# W706C.net
KiCad netlist of a schematic drawn in EAGLE
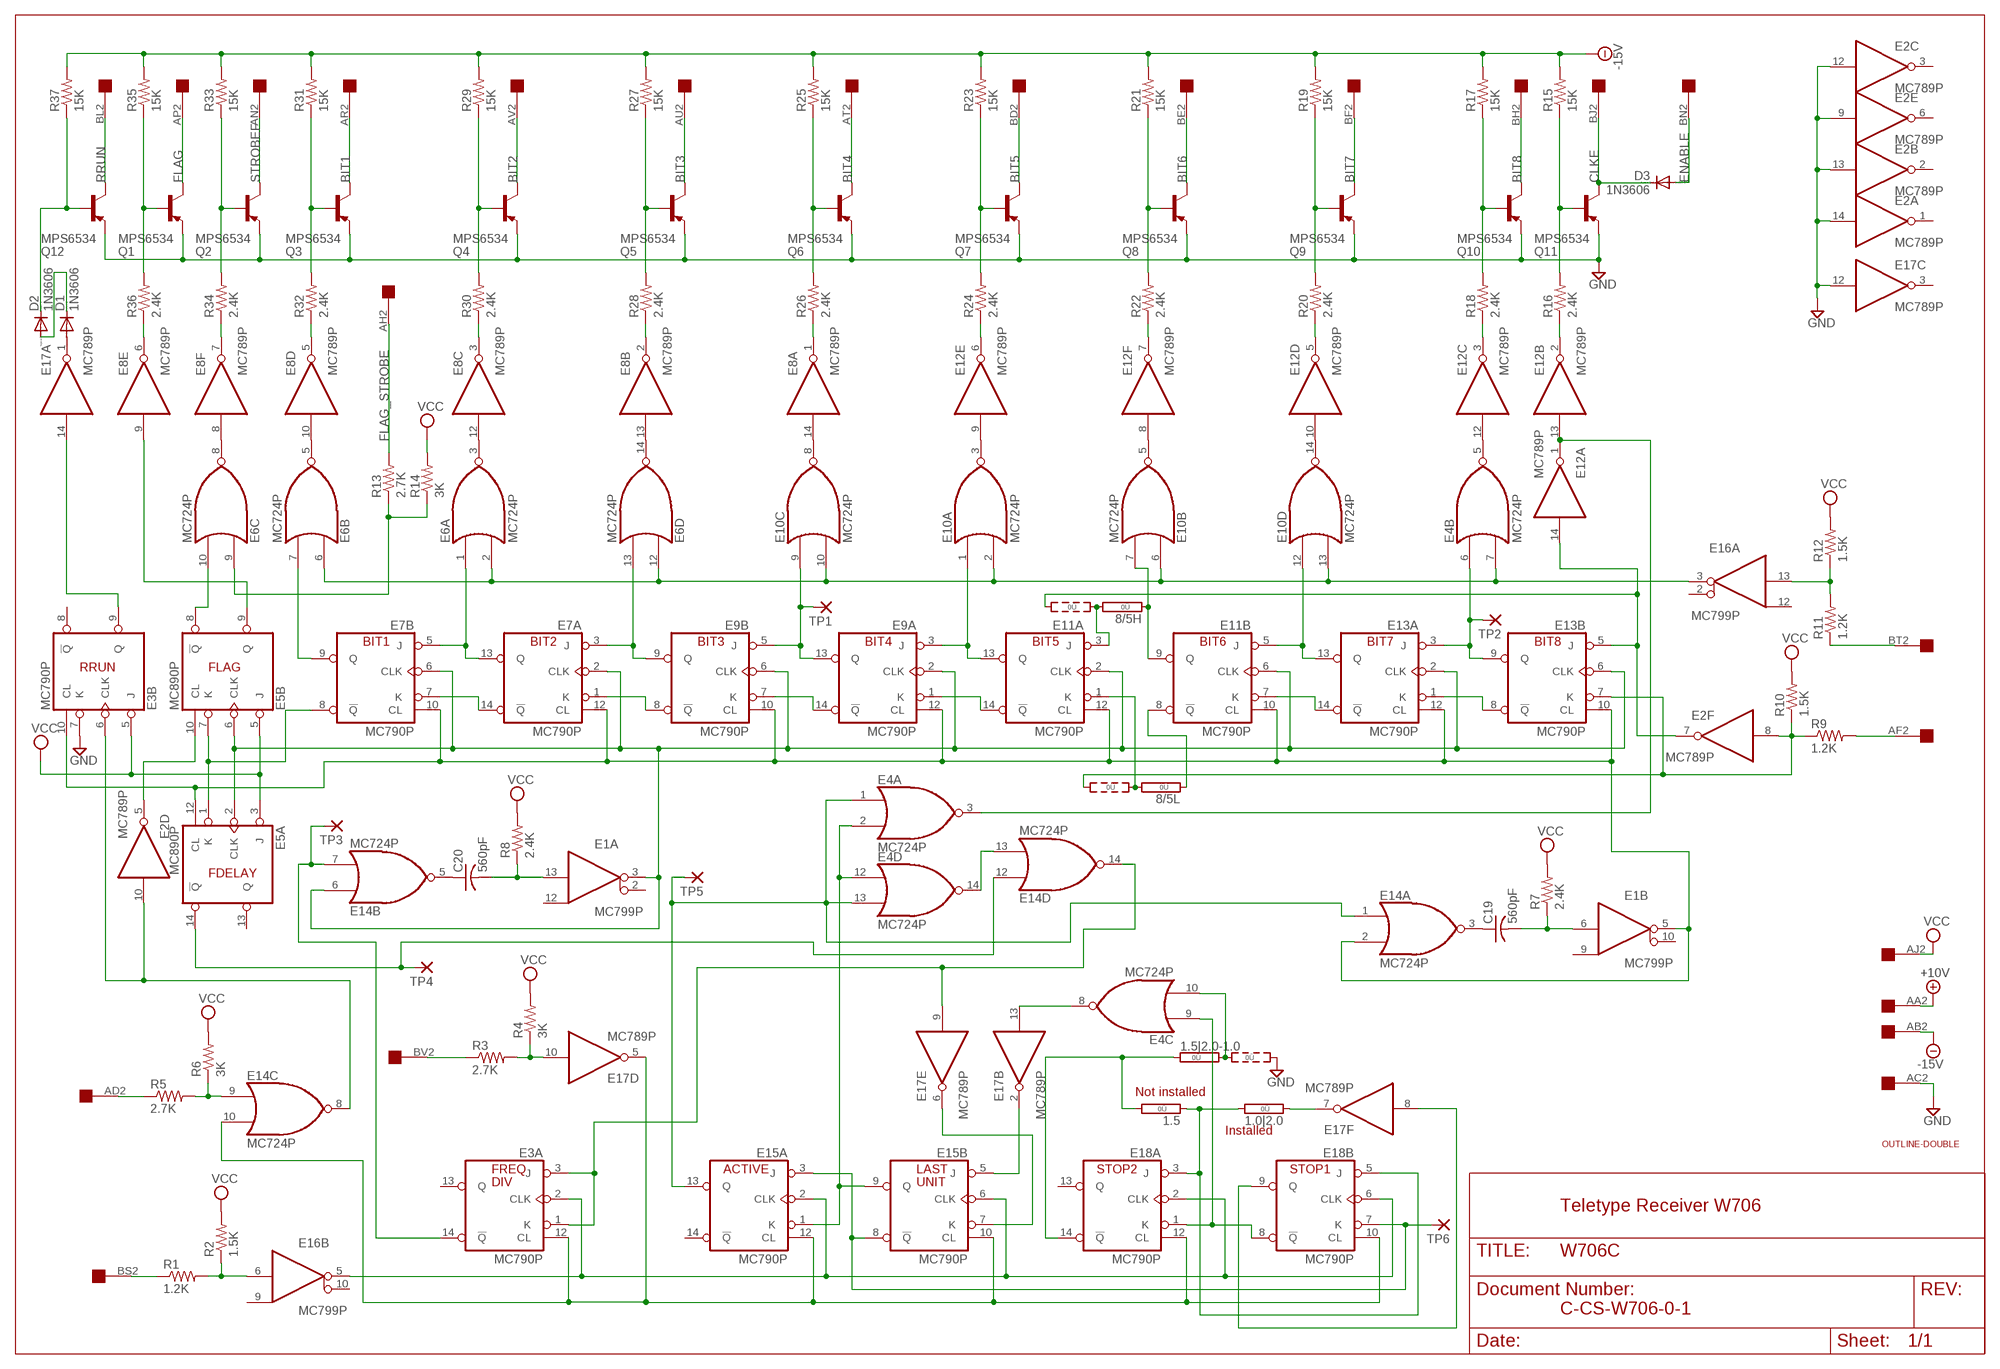
[diagram p0: schematic, sheet 1]

(export (version "E")
  (design (tool "Eeschema 10.0.6"))
  (components
    (comp (ref "1.0|2.0")
      (value "0R")
      (footprint "eagle-import:0R_10")
      (libsource (lib "eagle-import") (part "0R"))
    )
    (comp (ref "1.5")
      (value "0R")
      (footprint "eagle-import:0R_10")
      (libsource (lib "eagle-import") (part "0R"))
    )
    (comp (ref "1.5|2.0-1.0")
      (value "0R2")
      (footprint "eagle-import:0R2_10")
      (libsource (lib "eagle-import") (part "0R2"))
    )
    (comp (ref "8/5H")
      (value "0R2")
      (footprint "eagle-import:0R2_10")
      (libsource (lib "eagle-import") (part "0R2"))
    )
    (comp (ref "8/5L")
      (value "0R2")
      (footprint "eagle-import:0R2_10")
      (libsource (lib "eagle-import") (part "0R2"))
    )
    (comp (ref "C19")
      (value "560pF")
      (footprint "eagle-import:C050-025X075")
      (libsource (lib "eagle-import") (part "C-US050-025X075"))
    )
    (comp (ref "C20")
      (value "560pF")
      (footprint "eagle-import:C050-025X075")
      (libsource (lib "eagle-import") (part "C-US050-025X075"))
    )
    (comp (ref "D1")
      (value "1N3606")
      (footprint "eagle-import:DO35-10")
      (libsource (lib "eagle-import") (part "1N4148DO35-10"))
    )
    (comp (ref "D2")
      (value "1N3606")
      (footprint "eagle-import:DO35-10")
      (libsource (lib "eagle-import") (part "1N4148DO35-10"))
    )
    (comp (ref "D3")
      (value "1N3606")
      (footprint "eagle-import:DO35-10")
      (libsource (lib "eagle-import") (part "1N4148DO35-10"))
    )
    (comp (ref "E1")
      (value "MC799P")
      (footprint "eagle-import:DIL14")
      (libsource (lib "eagle-import") (part "MC899P"))
    )
    (comp (ref "E2")
      (value "MC789P")
      (footprint "eagle-import:DIL14")
      (libsource (lib "eagle-import") (part "MC889P"))
    )
    (comp (ref "E3")
      (value "MC790P")
      (footprint "eagle-import:DIL14")
      (libsource (lib "eagle-import") (part "MC890P"))
    )
    (comp (ref "E4")
      (value "MC724P")
      (footprint "eagle-import:DIL14")
      (libsource (lib "eagle-import") (part "MC824P"))
    )
    (comp (ref "E5")
      (value "MC890P")
      (footprint "eagle-import:DIL14")
      (libsource (lib "eagle-import") (part "MC890P"))
    )
    (comp (ref "E6")
      (value "MC724P")
      (footprint "eagle-import:DIL14")
      (libsource (lib "eagle-import") (part "MC824P"))
    )
    (comp (ref "E7")
      (value "MC790P")
      (footprint "eagle-import:DIL14")
      (libsource (lib "eagle-import") (part "MC890P"))
    )
    (comp (ref "E8")
      (value "MC789P")
      (footprint "eagle-import:DIL14")
      (libsource (lib "eagle-import") (part "MC889P"))
    )
    (comp (ref "E9")
      (value "MC790P")
      (footprint "eagle-import:DIL14")
      (libsource (lib "eagle-import") (part "MC890P"))
    )
    (comp (ref "E10")
      (value "MC724P")
      (footprint "eagle-import:DIL14")
      (libsource (lib "eagle-import") (part "MC824P"))
    )
    (comp (ref "E11")
      (value "MC790P")
      (footprint "eagle-import:DIL14")
      (libsource (lib "eagle-import") (part "MC890P"))
    )
    (comp (ref "E12")
      (value "MC789P")
      (footprint "eagle-import:DIL14")
      (libsource (lib "eagle-import") (part "MC889P"))
    )
    (comp (ref "E13")
      (value "MC790P")
      (footprint "eagle-import:DIL14")
      (libsource (lib "eagle-import") (part "MC890P"))
    )
    (comp (ref "E14")
      (value "MC724P")
      (footprint "eagle-import:DIL14")
      (libsource (lib "eagle-import") (part "MC824P"))
    )
    (comp (ref "E15")
      (value "MC790P")
      (footprint "eagle-import:DIL14")
      (libsource (lib "eagle-import") (part "MC890P"))
    )
    (comp (ref "E16")
      (value "MC799P")
      (footprint "eagle-import:DIL14")
      (libsource (lib "eagle-import") (part "MC899P"))
    )
    (comp (ref "E17")
      (value "MC789P")
      (footprint "eagle-import:DIL14")
      (libsource (lib "eagle-import") (part "MC889P"))
    )
    (comp (ref "E18")
      (value "MC790P")
      (footprint "eagle-import:DIL14")
      (libsource (lib "eagle-import") (part "MC890P"))
    )
    (comp (ref "Q1")
      (value "MPS6534")
      (footprint "eagle-import:TO39")
      (libsource (lib "eagle-import") (part "2N2904"))
    )
    (comp (ref "Q2")
      (value "MPS6534")
      (footprint "eagle-import:TO39")
      (libsource (lib "eagle-import") (part "2N2904"))
    )
    (comp (ref "Q3")
      (value "MPS6534")
      (footprint "eagle-import:TO39")
      (libsource (lib "eagle-import") (part "2N2904"))
    )
    (comp (ref "Q4")
      (value "MPS6534")
      (footprint "eagle-import:TO39")
      (libsource (lib "eagle-import") (part "2N2904"))
    )
    (comp (ref "Q5")
      (value "MPS6534")
      (footprint "eagle-import:TO39")
      (libsource (lib "eagle-import") (part "2N2904"))
    )
    (comp (ref "Q6")
      (value "MPS6534")
      (footprint "eagle-import:TO39")
      (libsource (lib "eagle-import") (part "2N2904"))
    )
    (comp (ref "Q7")
      (value "MPS6534")
      (footprint "eagle-import:TO39")
      (libsource (lib "eagle-import") (part "2N2904"))
    )
    (comp (ref "Q8")
      (value "MPS6534")
      (footprint "eagle-import:TO39")
      (libsource (lib "eagle-import") (part "2N2904"))
    )
    (comp (ref "Q9")
      (value "MPS6534")
      (footprint "eagle-import:TO39")
      (libsource (lib "eagle-import") (part "2N2904"))
    )
    (comp (ref "Q10")
      (value "MPS6534")
      (footprint "eagle-import:TO39")
      (libsource (lib "eagle-import") (part "2N2904"))
    )
    (comp (ref "Q11")
      (value "MPS6534")
      (footprint "eagle-import:TO39")
      (libsource (lib "eagle-import") (part "2N2904"))
    )
    (comp (ref "Q12")
      (value "MPS6534")
      (footprint "eagle-import:TO39")
      (libsource (lib "eagle-import") (part "2N2904"))
    )
    (comp (ref "R1")
      (value "1.2K")
      (footprint "eagle-import:0207_10")
      (libsource (lib "eagle-import") (part "R-US_0207/10"))
    )
    (comp (ref "R2")
      (value "1.5K")
      (footprint "eagle-import:0207_10")
      (libsource (lib "eagle-import") (part "R-US_0207/10"))
    )
    (comp (ref "R3")
      (value "2.7K")
      (footprint "eagle-import:0207_10")
      (libsource (lib "eagle-import") (part "R-US_0207/10"))
    )
    (comp (ref "R4")
      (value "3K")
      (footprint "eagle-import:0207_10")
      (libsource (lib "eagle-import") (part "R-US_0207/10"))
    )
    (comp (ref "R5")
      (value "2.7K")
      (footprint "eagle-import:0207_10")
      (libsource (lib "eagle-import") (part "R-US_0207/10"))
    )
    (comp (ref "R6")
      (value "3K")
      (footprint "eagle-import:0207_10")
      (libsource (lib "eagle-import") (part "R-US_0207/10"))
    )
    (comp (ref "R7")
      (value "2.4K")
      (footprint "eagle-import:0207_10")
      (libsource (lib "eagle-import") (part "R-US_0207/10"))
    )
    (comp (ref "R8")
      (value "2.4K")
      (footprint "eagle-import:0207_10")
      (libsource (lib "eagle-import") (part "R-US_0207/10"))
    )
    (comp (ref "R9")
      (value "1.2K")
      (footprint "eagle-import:0207_10")
      (libsource (lib "eagle-import") (part "R-US_0207/10"))
    )
    (comp (ref "R10")
      (value "1.5K")
      (footprint "eagle-import:0207_10")
      (libsource (lib "eagle-import") (part "R-US_0207/10"))
    )
    (comp (ref "R11")
      (value "1.2K")
      (footprint "eagle-import:0207_10")
      (libsource (lib "eagle-import") (part "R-US_0207/10"))
    )
    (comp (ref "R12")
      (value "1.5K")
      (footprint "eagle-import:0207_10")
      (libsource (lib "eagle-import") (part "R-US_0207/10"))
    )
    (comp (ref "R13")
      (value "2.7K")
      (footprint "eagle-import:0207_10")
      (libsource (lib "eagle-import") (part "R-US_0207/10"))
    )
    (comp (ref "R14")
      (value "3K")
      (footprint "eagle-import:0207_10")
      (libsource (lib "eagle-import") (part "R-US_0207/10"))
    )
    (comp (ref "R15")
      (value "15K")
      (footprint "eagle-import:0207_10")
      (libsource (lib "eagle-import") (part "R-US_0207/10"))
    )
    (comp (ref "R16")
      (value "2.4K")
      (footprint "eagle-import:0207_10")
      (libsource (lib "eagle-import") (part "R-US_0207/10"))
    )
    (comp (ref "R17")
      (value "15K")
      (footprint "eagle-import:0207_10")
      (libsource (lib "eagle-import") (part "R-US_0207/10"))
    )
    (comp (ref "R18")
      (value "2.4K")
      (footprint "eagle-import:0207_10")
      (libsource (lib "eagle-import") (part "R-US_0207/10"))
    )
    (comp (ref "R19")
      (value "15K")
      (footprint "eagle-import:0207_10")
      (libsource (lib "eagle-import") (part "R-US_0207/10"))
    )
    (comp (ref "R20")
      (value "2.4K")
      (footprint "eagle-import:0207_10")
      (libsource (lib "eagle-import") (part "R-US_0207/10"))
    )
    (comp (ref "R21")
      (value "15K")
      (footprint "eagle-import:0207_10")
      (libsource (lib "eagle-import") (part "R-US_0207/10"))
    )
    (comp (ref "R22")
      (value "2.4K")
      (footprint "eagle-import:0207_10")
      (libsource (lib "eagle-import") (part "R-US_0207/10"))
    )
    (comp (ref "R23")
      (value "15K")
      (footprint "eagle-import:0207_10")
      (libsource (lib "eagle-import") (part "R-US_0207/10"))
    )
    (comp (ref "R24")
      (value "2.4K")
      (footprint "eagle-import:0207_10")
      (libsource (lib "eagle-import") (part "R-US_0207/10"))
    )
    (comp (ref "R25")
      (value "15K")
      (footprint "eagle-import:0207_10")
      (libsource (lib "eagle-import") (part "R-US_0207/10"))
    )
    (comp (ref "R26")
      (value "2.4K")
      (footprint "eagle-import:0207_10")
      (libsource (lib "eagle-import") (part "R-US_0207/10"))
    )
    (comp (ref "R27")
      (value "15K")
      (footprint "eagle-import:0207_10")
      (libsource (lib "eagle-import") (part "R-US_0207/10"))
    )
    (comp (ref "R28")
      (value "2.4K")
      (footprint "eagle-import:0207_10")
      (libsource (lib "eagle-import") (part "R-US_0207/10"))
    )
    (comp (ref "R29")
      (value "15K")
      (footprint "eagle-import:0207_10")
      (libsource (lib "eagle-import") (part "R-US_0207/10"))
    )
    (comp (ref "R30")
      (value "2.4K")
      (footprint "eagle-import:0207_10")
      (libsource (lib "eagle-import") (part "R-US_0207/10"))
    )
    (comp (ref "R31")
      (value "15K")
      (footprint "eagle-import:0207_10")
      (libsource (lib "eagle-import") (part "R-US_0207/10"))
    )
    (comp (ref "R32")
      (value "2.4K")
      (footprint "eagle-import:0207_10")
      (libsource (lib "eagle-import") (part "R-US_0207/10"))
    )
    (comp (ref "R33")
      (value "15K")
      (footprint "eagle-import:0207_10")
      (libsource (lib "eagle-import") (part "R-US_0207/10"))
    )
    (comp (ref "R34")
      (value "2.4K")
      (footprint "eagle-import:0207_10")
      (libsource (lib "eagle-import") (part "R-US_0207/10"))
    )
    (comp (ref "R35")
      (value "15K")
      (footprint "eagle-import:0207_10")
      (libsource (lib "eagle-import") (part "R-US_0207/10"))
    )
    (comp (ref "R36")
      (value "2.4K")
      (footprint "eagle-import:0207_10")
      (libsource (lib "eagle-import") (part "R-US_0207/10"))
    )
    (comp (ref "R37")
      (value "15K")
      (footprint "eagle-import:0207_10")
      (libsource (lib "eagle-import") (part "R-US_0207/10"))
    )
    (comp (ref "TP1")
      (value "3,17/1,3")
      (footprint "eagle-import:3,17_1,3")
      (libsource (lib "eagle-import") (part "3,17/1,3"))
    )
    (comp (ref "TP2")
      (value "3,17/1,3")
      (footprint "eagle-import:3,17_1,3")
      (libsource (lib "eagle-import") (part "3,17/1,3"))
    )
    (comp (ref "TP3")
      (value "3,17/1,3")
      (footprint "eagle-import:3,17_1,3")
      (libsource (lib "eagle-import") (part "3,17/1,3"))
    )
    (comp (ref "TP4")
      (value "3,17/1,3")
      (footprint "eagle-import:3,17_1,3")
      (libsource (lib "eagle-import") (part "3,17/1,3"))
    )
    (comp (ref "TP5")
      (value "3,17/1,3")
      (footprint "eagle-import:3,17_1,3")
      (libsource (lib "eagle-import") (part "3,17/1,3"))
    )
    (comp (ref "TP6")
      (value "3,17/1,3")
      (footprint "eagle-import:3,17_1,3")
      (libsource (lib "eagle-import") (part "3,17/1,3"))
    )
    (comp (ref "U$1")
      (value "OUTLINE-DOUBLE")
      (footprint "eagle-import:DOUBLE")
      (libsource (lib "eagle-import") (part "OUTLINE-DOUBLE"))
    )
    (comp (ref "U$2")
      (value "DOUBLE")
      (footprint "eagle-import:EDGE-CON4")
      (libsource (lib "eagle-import") (part "DOUBLE"))
    )
  )
  (nets
    (net (code "1") (name "+10V") (class "Default")
      (node (ref "U$2") (pin "AA2") (pinfunction "1_AA2") (pintype "bidirectional"))
    )
    (net (code "2") (name "-15V") (class "Default")
      (node (ref "R15") (pin "2") (pinfunction "2_2") (pintype "passive"))
      (node (ref "R17") (pin "2") (pinfunction "2_2") (pintype "passive"))
      (node (ref "R19") (pin "2") (pinfunction "2_2") (pintype "passive"))
      (node (ref "R21") (pin "2") (pinfunction "2_2") (pintype "passive"))
      (node (ref "R23") (pin "2") (pinfunction "2_2") (pintype "passive"))
      (node (ref "R25") (pin "2") (pinfunction "2_2") (pintype "passive"))
      (node (ref "R27") (pin "2") (pinfunction "2_2") (pintype "passive"))
      (node (ref "R29") (pin "2") (pinfunction "2_2") (pintype "passive"))
      (node (ref "R31") (pin "2") (pinfunction "2_2") (pintype "passive"))
      (node (ref "R33") (pin "2") (pinfunction "2_2") (pintype "passive"))
      (node (ref "R35") (pin "2") (pinfunction "2_2") (pintype "passive"))
      (node (ref "R37") (pin "2") (pinfunction "2_2") (pintype "passive"))
      (node (ref "U$2") (pin "AB2") (pinfunction "1_AB2") (pintype "bidirectional"))
    )
    (net (code "3") (name "/BIT1") (class "Default")
      (node (ref "Q3") (pin "3") (pinfunction "C_3") (pintype "passive"))
      (node (ref "U$2") (pin "AR2") (pinfunction "1_AR2") (pintype "bidirectional"))
    )
    (net (code "4") (name "/BIT2") (class "Default")
      (node (ref "Q4") (pin "3") (pinfunction "C_3") (pintype "passive"))
      (node (ref "U$2") (pin "AV2") (pinfunction "1_AV2") (pintype "bidirectional"))
    )
    (net (code "5") (name "/BIT3") (class "Default")
      (node (ref "Q5") (pin "3") (pinfunction "C_3") (pintype "passive"))
      (node (ref "U$2") (pin "AU2") (pinfunction "1_AU2") (pintype "bidirectional"))
    )
    (net (code "6") (name "/BIT4") (class "Default")
      (node (ref "Q6") (pin "3") (pinfunction "C_3") (pintype "passive"))
      (node (ref "U$2") (pin "AT2") (pinfunction "1_AT2") (pintype "bidirectional"))
    )
    (net (code "7") (name "/BIT5") (class "Default")
      (node (ref "Q7") (pin "3") (pinfunction "C_3") (pintype "passive"))
      (node (ref "U$2") (pin "BD2") (pinfunction "1_BD2") (pintype "bidirectional"))
    )
    (net (code "8") (name "/BIT6") (class "Default")
      (node (ref "Q8") (pin "3") (pinfunction "C_3") (pintype "passive"))
      (node (ref "U$2") (pin "BE2") (pinfunction "1_BE2") (pintype "bidirectional"))
    )
    (net (code "9") (name "/BIT7") (class "Default")
      (node (ref "Q9") (pin "3") (pinfunction "C_3") (pintype "passive"))
      (node (ref "U$2") (pin "BF2") (pinfunction "1_BF2") (pintype "bidirectional"))
    )
    (net (code "10") (name "/BIT8") (class "Default")
      (node (ref "Q10") (pin "3") (pinfunction "C_3") (pintype "passive"))
      (node (ref "U$2") (pin "BH2") (pinfunction "1_BH2") (pintype "bidirectional"))
    )
    (net (code "11") (name "/CLKE") (class "Default")
      (node (ref "D3") (pin "C") (pinfunction "C_C") (pintype "passive"))
      (node (ref "Q11") (pin "3") (pinfunction "C_3") (pintype "passive"))
      (node (ref "U$2") (pin "BJ2") (pinfunction "1_BJ2") (pintype "bidirectional"))
    )
    (net (code "12") (name "/ENABLE") (class "Default")
      (node (ref "D3") (pin "A") (pinfunction "A_A") (pintype "passive"))
      (node (ref "U$2") (pin "BN2") (pinfunction "1_BN2") (pintype "bidirectional"))
    )
    (net (code "13") (name "/FLAG") (class "Default")
      (node (ref "Q1") (pin "3") (pinfunction "C_3") (pintype "passive"))
      (node (ref "U$2") (pin "AP2") (pinfunction "1_AP2") (pintype "bidirectional"))
    )
    (net (code "14") (name "/FLAG_STROBE") (class "Default")
      (node (ref "R13") (pin "2") (pinfunction "2_2") (pintype "passive"))
      (node (ref "U$2") (pin "AH2") (pinfunction "1_AH2") (pintype "bidirectional"))
    )
    (net (code "15") (name "/RRUN") (class "Default")
      (node (ref "Q12") (pin "3") (pinfunction "C_3") (pintype "passive"))
      (node (ref "U$2") (pin "BL2") (pinfunction "1_BL2") (pintype "bidirectional"))
    )
    (net (code "16") (name "/STROBEF") (class "Default")
      (node (ref "Q2") (pin "3") (pinfunction "C_3") (pintype "passive"))
      (node (ref "U$2") (pin "AN2") (pinfunction "1_AN2") (pintype "bidirectional"))
    )
    (net (code "17") (name "GND") (class "Default")
      (node (ref "1.5|2.0-1.0") (pin "3") (pinfunction "3_3") (pintype "passive"))
      (node (ref "E17") (pin "12") (pinfunction "I_12") (pintype "input"))
      (node (ref "E2") (pin "12") (pinfunction "I_12") (pintype "input"))
      (node (ref "E2") (pin "13") (pinfunction "I_13") (pintype "input"))
      (node (ref "E2") (pin "14") (pinfunction "I_14") (pintype "input"))
      (node (ref "E2") (pin "9") (pinfunction "I_9") (pintype "input"))
      (node (ref "E3") (pin "7") (pinfunction "K_7") (pintype "input"))
      (node (ref "Q1") (pin "1") (pinfunction "E_1") (pintype "passive"))
      (node (ref "Q10") (pin "1") (pinfunction "E_1") (pintype "passive"))
      (node (ref "Q11") (pin "1") (pinfunction "E_1") (pintype "passive"))
      (node (ref "Q12") (pin "1") (pinfunction "E_1") (pintype "passive"))
      (node (ref "Q2") (pin "1") (pinfunction "E_1") (pintype "passive"))
      (node (ref "Q3") (pin "1") (pinfunction "E_1") (pintype "passive"))
      (node (ref "Q4") (pin "1") (pinfunction "E_1") (pintype "passive"))
      (node (ref "Q5") (pin "1") (pinfunction "E_1") (pintype "passive"))
      (node (ref "Q6") (pin "1") (pinfunction "E_1") (pintype "passive"))
      (node (ref "Q7") (pin "1") (pinfunction "E_1") (pintype "passive"))
      (node (ref "Q8") (pin "1") (pinfunction "E_1") (pintype "passive"))
      (node (ref "Q9") (pin "1") (pinfunction "E_1") (pintype "passive"))
      (node (ref "U$2") (pin "AC2") (pinfunction "1_AC2") (pintype "bidirectional"))
    )
    (net (code "18") (name "Net-(D1-PadC)") (class "Default")
      (node (ref "D1") (pin "C") (pinfunction "C_C") (pintype "passive"))
      (node (ref "D2") (pin "A") (pinfunction "A_A") (pintype "passive"))
    )
    (net (code "19") (name "Net-(E1A-I)") (class "Default")
      (node (ref "C20") (pin "2") (pinfunction "2_2") (pintype "passive"))
      (node (ref "E1") (pin "13") (pinfunction "I_13") (pintype "input"))
      (node (ref "R8") (pin "1") (pinfunction "1_1") (pintype "passive"))
    )
    (net (code "20") (name "Net-(E1B-I)") (class "Default")
      (node (ref "C19") (pin "2") (pinfunction "2_2") (pintype "passive"))
      (node (ref "E1") (pin "6") (pinfunction "I_6") (pintype "input"))
      (node (ref "R7") (pin "1") (pinfunction "1_1") (pintype "passive"))
    )
    (net (code "21") (name "Net-(E2D-O)") (class "Default")
      (node (ref "E2") (pin "5") (pinfunction "O_5") (pintype "output"))
      (node (ref "E5") (pin "10") (pinfunction "CL_10") (pintype "input"))
    )
    (net (code "22") (name "Net-(E4C-I1)") (class "Default")
      (node (ref "1.5|2.0-1.0") (pin "2") (pinfunction "2_2") (pintype "passive"))
      (node (ref "E4") (pin "10") (pinfunction "I1_10") (pintype "input"))
    )
    (net (code "23") (name "Net-(E5A-K)") (class "Default")
      (node (ref "E5") (pin "1") (pinfunction "K_1") (pintype "input"))
      (node (ref "E5") (pin "7") (pinfunction "K_7") (pintype "input"))
      (node (ref "E7") (pin "8") (pinfunction "~{Q}_8") (pintype "output"))
    )
    (net (code "24") (name "Net-(E5B-Q)") (class "Default")
      (node (ref "E5") (pin "9") (pinfunction "Q_9") (pintype "output"))
      (node (ref "E8") (pin "9") (pinfunction "I_9") (pintype "input"))
    )
    (net (code "25") (name "Net-(E5B-~{Q})") (class "Default")
      (node (ref "E5") (pin "8") (pinfunction "~{Q}_8") (pintype "output"))
      (node (ref "E6") (pin "10") (pinfunction "I1_10") (pintype "input"))
    )
    (net (code "26") (name "Net-(E6A-I0)") (class "Default")
      (node (ref "E6") (pin "1") (pinfunction "I0_1") (pintype "input"))
      (node (ref "E7") (pin "13") (pinfunction "Q_13") (pintype "output"))
      (node (ref "E7") (pin "5") (pinfunction "J_5") (pintype "input"))
    )
    (net (code "27") (name "Net-(E6A-O)") (class "Default")
      (node (ref "E6") (pin "3") (pinfunction "O_3") (pintype "output"))
      (node (ref "E8") (pin "12") (pinfunction "I_12") (pintype "input"))
    )
    (net (code "28") (name "Net-(E6B-I1)") (class "Default")
      (node (ref "E6") (pin "7") (pinfunction "I1_7") (pintype "input"))
      (node (ref "E7") (pin "9") (pinfunction "Q_9") (pintype "output"))
    )
    (net (code "29") (name "Net-(E6B-O)") (class "Default")
      (node (ref "E6") (pin "5") (pinfunction "O_5") (pintype "output"))
      (node (ref "E8") (pin "10") (pinfunction "I_10") (pintype "input"))
    )
    (net (code "30") (name "Net-(E6C-I0)") (class "Default")
      (node (ref "E6") (pin "9") (pinfunction "I0_9") (pintype "input"))
      (node (ref "R13") (pin "1") (pinfunction "1_1") (pintype "passive"))
      (node (ref "R14") (pin "1") (pinfunction "1_1") (pintype "passive"))
    )
    (net (code "31") (name "Net-(E6C-O)") (class "Default")
      (node (ref "E6") (pin "8") (pinfunction "O_8") (pintype "output"))
      (node (ref "E8") (pin "8") (pinfunction "I_8") (pintype "input"))
    )
    (net (code "32") (name "Net-(E6D-I1)") (class "Default")
      (node (ref "E6") (pin "13") (pinfunction "I1_13") (pintype "input"))
      (node (ref "E7") (pin "3") (pinfunction "J_3") (pintype "input"))
      (node (ref "E9") (pin "9") (pinfunction "Q_9") (pintype "output"))
    )
    (net (code "33") (name "Net-(E6D-O)") (class "Default")
      (node (ref "E6") (pin "14") (pinfunction "O_14") (pintype "output"))
      (node (ref "E8") (pin "13") (pinfunction "I_13") (pintype "input"))
    )
    (net (code "34") (name "Net-(E7A-K)") (class "Default")
      (node (ref "E7") (pin "1") (pinfunction "K_1") (pintype "input"))
      (node (ref "E9") (pin "8") (pinfunction "~{Q}_8") (pintype "output"))
    )
    (net (code "35") (name "Net-(E7A-~{Q})") (class "Default")
      (node (ref "E7") (pin "14") (pinfunction "~{Q}_14") (pintype "output"))
      (node (ref "E7") (pin "7") (pinfunction "K_7") (pintype "input"))
    )
    (net (code "36") (name "Net-(E8A-O)") (class "Default")
      (node (ref "E8") (pin "1") (pinfunction "O_1") (pintype "output"))
      (node (ref "R26") (pin "1") (pinfunction "1_1") (pintype "passive"))
    )
    (net (code "37") (name "Net-(E8B-O)") (class "Default")
      (node (ref "E8") (pin "2") (pinfunction "O_2") (pintype "output"))
      (node (ref "R28") (pin "1") (pinfunction "1_1") (pintype "passive"))
    )
    (net (code "38") (name "Net-(E8C-O)") (class "Default")
      (node (ref "E8") (pin "3") (pinfunction "O_3") (pintype "output"))
      (node (ref "R30") (pin "1") (pinfunction "1_1") (pintype "passive"))
    )
    (net (code "39") (name "Net-(E8D-O)") (class "Default")
      (node (ref "E8") (pin "5") (pinfunction "O_5") (pintype "output"))
      (node (ref "R32") (pin "1") (pinfunction "1_1") (pintype "passive"))
    )
    (net (code "40") (name "Net-(E8E-O)") (class "Default")
      (node (ref "E8") (pin "6") (pinfunction "O_6") (pintype "output"))
      (node (ref "R36") (pin "1") (pinfunction "1_1") (pintype "passive"))
    )
    (net (code "41") (name "Net-(E8F-O)") (class "Default")
      (node (ref "E8") (pin "7") (pinfunction "O_7") (pintype "output"))
      (node (ref "R34") (pin "1") (pinfunction "1_1") (pintype "passive"))
    )
    (net (code "42") (name "Net-(E9A-~{Q})") (class "Default")
      (node (ref "E9") (pin "14") (pinfunction "~{Q}_14") (pintype "output"))
      (node (ref "E9") (pin "7") (pinfunction "K_7") (pintype "input"))
    )
    (net (code "43") (name "Net-(E10A-I0)") (class "Default")
      (node (ref "E10") (pin "1") (pinfunction "I0_1") (pintype "input"))
      (node (ref "E11") (pin "13") (pinfunction "Q_13") (pintype "output"))
      (node (ref "E9") (pin "3") (pinfunction "J_3") (pintype "input"))
    )
    (net (code "44") (name "Net-(E10A-I1)") (class "Default")
      (node (ref "E10") (pin "10") (pinfunction "I1_10") (pintype "input"))
      (node (ref "E10") (pin "13") (pinfunction "I1_13") (pintype "input"))
      (node (ref "E10") (pin "2") (pinfunction "I1_2") (pintype "input"))
      (node (ref "E10") (pin "6") (pinfunction "I0_6") (pintype "input"))
      (node (ref "E16") (pin "3") (pinfunction "O_3") (pintype "output"))
      (node (ref "E4") (pin "7") (pinfunction "I1_7") (pintype "input"))
      (node (ref "E6") (pin "12") (pinfunction "I0_12") (pintype "input"))
      (node (ref "E6") (pin "2") (pinfunction "I1_2") (pintype "input"))
      (node (ref "E6") (pin "6") (pinfunction "I0_6") (pintype "input"))
    )
    (net (code "45") (name "Net-(E10A-O)") (class "Default")
      (node (ref "E10") (pin "3") (pinfunction "O_3") (pintype "output"))
      (node (ref "E12") (pin "9") (pinfunction "I_9") (pintype "input"))
    )
    (net (code "46") (name "Net-(E10B-I1)") (class "Default")
      (node (ref "8/5H") (pin "1") (pinfunction "1_1") (pintype "passive"))
      (node (ref "E10") (pin "7") (pinfunction "I1_7") (pintype "input"))
      (node (ref "E11") (pin "9") (pinfunction "Q_9") (pintype "output"))
    )
    (net (code "47") (name "Net-(E10B-O)") (class "Default")
      (node (ref "E10") (pin "5") (pinfunction "O_5") (pintype "output"))
      (node (ref "E12") (pin "8") (pinfunction "I_8") (pintype "input"))
    )
    (net (code "48") (name "Net-(E10C-I0)") (class "Default")
      (node (ref "E10") (pin "9") (pinfunction "I0_9") (pintype "input"))
      (node (ref "E9") (pin "13") (pinfunction "Q_13") (pintype "output"))
      (node (ref "E9") (pin "5") (pinfunction "J_5") (pintype "input"))
      (node (ref "TP1") (pin "1") (pinfunction "P_1") (pintype "passive"))
    )
    (net (code "49") (name "Net-(E10C-O)") (class "Default")
      (node (ref "E10") (pin "8") (pinfunction "O_8") (pintype "output"))
      (node (ref "E8") (pin "14") (pinfunction "I_14") (pintype "input"))
    )
    (net (code "50") (name "Net-(E10D-I0)") (class "Default")
      (node (ref "E10") (pin "12") (pinfunction "I0_12") (pintype "input"))
      (node (ref "E11") (pin "5") (pinfunction "J_5") (pintype "input"))
      (node (ref "E13") (pin "13") (pinfunction "Q_13") (pintype "output"))
    )
    (net (code "51") (name "Net-(E10D-O)") (class "Default")
      (node (ref "E10") (pin "14") (pinfunction "O_14") (pintype "output"))
      (node (ref "E12") (pin "10") (pinfunction "I_10") (pintype "input"))
    )
    (net (code "52") (name "Net-(E11A-CL)") (class "Default")
      (node (ref "E1") (pin "5") (pinfunction "O_5") (pintype "output"))
      (node (ref "E11") (pin "10") (pinfunction "CL_10") (pintype "input"))
      (node (ref "E11") (pin "12") (pinfunction "CL_12") (pintype "input"))
      (node (ref "E13") (pin "10") (pinfunction "CL_10") (pintype "input"))
      (node (ref "E13") (pin "12") (pinfunction "CL_12") (pintype "input"))
      (node (ref "E14") (pin "2") (pinfunction "I1_2") (pintype "input"))
      (node (ref "E3") (pin "10") (pinfunction "CL_10") (pintype "input"))
      (node (ref "E5") (pin "12") (pinfunction "CL_12") (pintype "input"))
      (node (ref "E7") (pin "10") (pinfunction "CL_10") (pintype "input"))
      (node (ref "E7") (pin "12") (pinfunction "CL_12") (pintype "input"))
      (node (ref "E9") (pin "10") (pinfunction "CL_10") (pintype "input"))
      (node (ref "E9") (pin "12") (pinfunction "CL_12") (pintype "input"))
    )
    (net (code "53") (name "Net-(E11A-CLK)") (class "Default")
      (node (ref "E1") (pin "3") (pinfunction "O_3") (pintype "output"))
      (node (ref "E11") (pin "2") (pinfunction "CLK_2") (pintype "input"))
      (node (ref "E11") (pin "6") (pinfunction "CLK_6") (pintype "input"))
      (node (ref "E13") (pin "2") (pinfunction "CLK_2") (pintype "input"))
      (node (ref "E13") (pin "6") (pinfunction "CLK_6") (pintype "input"))
      (node (ref "E14") (pin "6") (pinfunction "I0_6") (pintype "input"))
      (node (ref "E5") (pin "2") (pinfunction "CLK_2") (pintype "input"))
      (node (ref "E5") (pin "6") (pinfunction "CLK_6") (pintype "input"))
      (node (ref "E7") (pin "2") (pinfunction "CLK_2") (pintype "input"))
      (node (ref "E7") (pin "6") (pinfunction "CLK_6") (pintype "input"))
      (node (ref "E9") (pin "2") (pinfunction "CLK_2") (pintype "input"))
      (node (ref "E9") (pin "6") (pinfunction "CLK_6") (pintype "input"))
    )
    (net (code "54") (name "Net-(E11A-J)") (class "Default")
      (node (ref "8/5H") (pin "2") (pinfunction "2_2") (pintype "passive"))
      (node (ref "E11") (pin "3") (pinfunction "J_3") (pintype "input"))
    )
    (net (code "55") (name "Net-(E11A-K)") (class "Default")
      (node (ref "8/5L") (pin "2") (pinfunction "2_2") (pintype "passive"))
      (node (ref "E11") (pin "1") (pinfunction "K_1") (pintype "input"))
    )
    (net (code "56") (name "Net-(E11A-~{Q})") (class "Default")
      (node (ref "E11") (pin "14") (pinfunction "~{Q}_14") (pintype "output"))
      (node (ref "E9") (pin "1") (pinfunction "K_1") (pintype "input"))
    )
    (net (code "57") (name "Net-(E11B-K)") (class "Default")
      (node (ref "E11") (pin "7") (pinfunction "K_7") (pintype "input"))
      (node (ref "E13") (pin "14") (pinfunction "~{Q}_14") (pintype "output"))
    )
    (net (code "58") (name "Net-(E11B-~{Q})") (class "Default")
      (node (ref "8/5L") (pin "1") (pinfunction "1_1") (pintype "passive"))
      (node (ref "E11") (pin "8") (pinfunction "~{Q}_8") (pintype "output"))
    )
    (net (code "59") (name "Net-(E12A-I)") (class "Default")
      (node (ref "8/5H") (pin "3") (pinfunction "3_3") (pintype "passive"))
      (node (ref "E12") (pin "14") (pinfunction "I_14") (pintype "input"))
      (node (ref "E13") (pin "5") (pinfunction "J_5") (pintype "input"))
      (node (ref "E2") (pin "7") (pinfunction "O_7") (pintype "output"))
    )
    (net (code "60") (name "Net-(E12A-O)") (class "Default")
      (node (ref "E12") (pin "1") (pinfunction "O_1") (pintype "output"))
      (node (ref "E12") (pin "13") (pinfunction "I_13") (pintype "input"))
      (node (ref "E4") (pin "3") (pinfunction "O_3") (pintype "output"))
    )
    (net (code "61") (name "Net-(E12B-O)") (class "Default")
      (node (ref "E12") (pin "2") (pinfunction "O_2") (pintype "output"))
      (node (ref "R16") (pin "1") (pinfunction "1_1") (pintype "passive"))
    )
    (net (code "62") (name "Net-(E12C-I)") (class "Default")
      (node (ref "E12") (pin "12") (pinfunction "I_12") (pintype "input"))
      (node (ref "E4") (pin "5") (pinfunction "O_5") (pintype "output"))
    )
    (net (code "63") (name "Net-(E12C-O)") (class "Default")
      (node (ref "E12") (pin "3") (pinfunction "O_3") (pintype "output"))
      (node (ref "R18") (pin "1") (pinfunction "1_1") (pintype "passive"))
    )
    (net (code "64") (name "Net-(E12D-O)") (class "Default")
      (node (ref "E12") (pin "5") (pinfunction "O_5") (pintype "output"))
      (node (ref "R20") (pin "1") (pinfunction "1_1") (pintype "passive"))
    )
    (net (code "65") (name "Net-(E12E-O)") (class "Default")
      (node (ref "E12") (pin "6") (pinfunction "O_6") (pintype "output"))
      (node (ref "R24") (pin "1") (pinfunction "1_1") (pintype "passive"))
    )
    (net (code "66") (name "Net-(E12F-O)") (class "Default")
      (node (ref "E12") (pin "7") (pinfunction "O_7") (pintype "output"))
      (node (ref "R22") (pin "1") (pinfunction "1_1") (pintype "passive"))
    )
    (net (code "67") (name "Net-(E13A-J)") (class "Default")
      (node (ref "E13") (pin "3") (pinfunction "J_3") (pintype "input"))
      (node (ref "E13") (pin "9") (pinfunction "Q_9") (pintype "output"))
      (node (ref "E4") (pin "6") (pinfunction "I0_6") (pintype "input"))
      (node (ref "TP2") (pin "1") (pinfunction "P_1") (pintype "passive"))
    )
    (net (code "68") (name "Net-(E13A-K)") (class "Default")
      (node (ref "E13") (pin "1") (pinfunction "K_1") (pintype "input"))
      (node (ref "E13") (pin "8") (pinfunction "~{Q}_8") (pintype "output"))
    )
    (net (code "69") (name "Net-(E13B-K)") (class "Default")
      (node (ref "8/5L") (pin "3") (pinfunction "3_3") (pintype "passive"))
      (node (ref "E13") (pin "7") (pinfunction "K_7") (pintype "input"))
      (node (ref "E2") (pin "8") (pinfunction "I_8") (pintype "input"))
      (node (ref "R10") (pin "1") (pinfunction "1_1") (pintype "passive"))
      (node (ref "R9") (pin "1") (pinfunction "1_1") (pintype "passive"))
    )
    (net (code "70") (name "Net-(E14A-I0)") (class "Default")
      (node (ref "E14") (pin "1") (pinfunction "I0_1") (pintype "input"))
      (node (ref "E15") (pin "13") (pinfunction "Q_13") (pintype "output"))
      (node (ref "E4") (pin "1") (pinfunction "I0_1") (pintype "input"))
      (node (ref "E4") (pin "13") (pinfunction "I1_13") (pintype "input"))
      (node (ref "TP5") (pin "1") (pinfunction "P_1") (pintype "passive"))
    )
    (net (code "71") (name "Net-(E14A-O)") (class "Default")
      (node (ref "C19") (pin "1") (pinfunction "1_1") (pintype "passive"))
      (node (ref "E14") (pin "3") (pinfunction "O_3") (pintype "output"))
    )
    (net (code "72") (name "Net-(E14B-I1)") (class "Default")
      (node (ref "E14") (pin "7") (pinfunction "I1_7") (pintype "input"))
      (node (ref "E3") (pin "14") (pinfunction "~{Q}_14") (pintype "output"))
      (node (ref "TP3") (pin "1") (pinfunction "P_1") (pintype "passive"))
    )
    (net (code "73") (name "Net-(E14B-O)") (class "Default")
      (node (ref "C20") (pin "1") (pinfunction "1_1") (pintype "passive"))
      (node (ref "E14") (pin "5") (pinfunction "O_5") (pintype "output"))
    )
    (net (code "74") (name "Net-(E14C-I0)") (class "Default")
      (node (ref "E14") (pin "9") (pinfunction "I0_9") (pintype "input"))
      (node (ref "R5") (pin "2") (pinfunction "2_2") (pintype "passive"))
      (node (ref "R6") (pin "1") (pinfunction "1_1") (pintype "passive"))
    )
    (net (code "75") (name "Net-(E14C-I1)") (class "Default")
      (node (ref "E14") (pin "10") (pinfunction "I1_10") (pintype "input"))
      (node (ref "E15") (pin "10") (pinfunction "CL_10") (pintype "input"))
      (node (ref "E15") (pin "12") (pinfunction "CL_12") (pintype "input"))
      (node (ref "E17") (pin "5") (pinfunction "O_5") (pintype "output"))
      (node (ref "E18") (pin "10") (pinfunction "CL_10") (pintype "input"))
      (node (ref "E18") (pin "12") (pinfunction "CL_12") (pintype "input"))
      (node (ref "E3") (pin "12") (pinfunction "CL_12") (pintype "input"))
    )
    (net (code "76") (name "Net-(E14C-O)") (class "Default")
      (node (ref "E14") (pin "8") (pinfunction "O_8") (pintype "output"))
      (node (ref "E2") (pin "10") (pinfunction "I_10") (pintype "input"))
      (node (ref "E3") (pin "6") (pinfunction "CLK_6") (pintype "input"))
    )
    (net (code "77") (name "Net-(E14D-I0)") (class "Default")
      (node (ref "E14") (pin "12") (pinfunction "I0_12") (pintype "input"))
      (node (ref "E5") (pin "14") (pinfunction "~{Q}_14") (pintype "output"))
      (node (ref "TP4") (pin "1") (pinfunction "P_1") (pintype "passive"))
    )
    (net (code "78") (name "Net-(E14D-I1)") (class "Default")
      (node (ref "E14") (pin "13") (pinfunction "I1_13") (pintype "input"))
      (node (ref "E4") (pin "14") (pinfunction "O_14") (pintype "output"))
    )
    (net (code "79") (name "Net-(E14D-O)") (class "Default")
      (node (ref "E14") (pin "14") (pinfunction "O_14") (pintype "output"))
      (node (ref "E17") (pin "9") (pinfunction "I_9") (pintype "input"))
      (node (ref "E3") (pin "1") (pinfunction "K_1") (pintype "input"))
      (node (ref "E3") (pin "3") (pinfunction "J_3") (pintype "input"))
    )
    (net (code "80") (name "Net-(E15A-CLK)") (class "Default")
      (node (ref "E15") (pin "2") (pinfunction "CLK_2") (pintype "input"))
      (node (ref "E15") (pin "6") (pinfunction "CLK_6") (pintype "input"))
      (node (ref "E16") (pin "5") (pinfunction "O_5") (pintype "output"))
      (node (ref "E18") (pin "2") (pinfunction "CLK_2") (pintype "input"))
      (node (ref "E18") (pin "6") (pinfunction "CLK_6") (pintype "input"))
      (node (ref "E3") (pin "2") (pinfunction "CLK_2") (pintype "input"))
    )
    (net (code "81") (name "Net-(E15A-J)") (class "Default")
      (node (ref "E15") (pin "3") (pinfunction "J_3") (pintype "input"))
      (node (ref "E15") (pin "8") (pinfunction "~{Q}_8") (pintype "output"))
      (node (ref "E18") (pin "7") (pinfunction "K_7") (pintype "input"))
      (node (ref "TP6") (pin "1") (pinfunction "P_1") (pintype "passive"))
    )
    (net (code "82") (name "Net-(E15A-K)") (class "Default")
      (node (ref "E15") (pin "1") (pinfunction "K_1") (pintype "input"))
      (node (ref "E15") (pin "9") (pinfunction "Q_9") (pintype "output"))
      (node (ref "E4") (pin "12") (pinfunction "I0_12") (pintype "input"))
      (node (ref "E4") (pin "2") (pinfunction "I1_2") (pintype "input"))
    )
    (net (code "83") (name "Net-(E15B-J)") (class "Default")
      (node (ref "E15") (pin "5") (pinfunction "J_5") (pintype "input"))
      (node (ref "E17") (pin "2") (pinfunction "O_2") (pintype "output"))
    )
    (net (code "84") (name "Net-(E15B-K)") (class "Default")
      (node (ref "E15") (pin "7") (pinfunction "K_7") (pintype "input"))
      (node (ref "E17") (pin "6") (pinfunction "O_6") (pintype "output"))
    )
    (net (code "85") (name "Net-(E16A-I)") (class "Default")
      (node (ref "E16") (pin "13") (pinfunction "I_13") (pintype "input"))
      (node (ref "R11") (pin "2") (pinfunction "2_2") (pintype "passive"))
      (node (ref "R12") (pin "1") (pinfunction "1_1") (pintype "passive"))
    )
    (net (code "86") (name "Net-(E16B-I)") (class "Default")
      (node (ref "E16") (pin "6") (pinfunction "I_6") (pintype "input"))
      (node (ref "R1") (pin "2") (pinfunction "2_2") (pintype "passive"))
      (node (ref "R2") (pin "1") (pinfunction "1_1") (pintype "passive"))
    )
    (net (code "87") (name "Net-(E17A-I)") (class "Default")
      (node (ref "E17") (pin "14") (pinfunction "I_14") (pintype "input"))
      (node (ref "E3") (pin "9") (pinfunction "Q_9") (pintype "output"))
    )
    (net (code "88") (name "Net-(E17A-O)") (class "Default")
      (node (ref "D1") (pin "A") (pinfunction "A_A") (pintype "passive"))
      (node (ref "E17") (pin "1") (pinfunction "O_1") (pintype "output"))
    )
    (net (code "89") (name "Net-(E17B-I)") (class "Default")
      (node (ref "E17") (pin "13") (pinfunction "I_13") (pintype "input"))
      (node (ref "E4") (pin "8") (pinfunction "O_8") (pintype "output"))
    )
    (net (code "90") (name "Net-(E17D-I)") (class "Default")
      (node (ref "E17") (pin "10") (pinfunction "I_10") (pintype "input"))
      (node (ref "R3") (pin "2") (pinfunction "2_2") (pintype "passive"))
      (node (ref "R4") (pin "1") (pinfunction "1_1") (pintype "passive"))
    )
    (net (code "91") (name "Net-(E17F-I)") (class "Default")
      (node (ref "E17") (pin "8") (pinfunction "I_8") (pintype "input"))
      (node (ref "E18") (pin "9") (pinfunction "Q_9") (pintype "output"))
    )
    (net (code "92") (name "Net-(E17F-O)") (class "Default")
      (node (ref "1.0|2.0") (pin "1") (pinfunction "1_1") (pintype "passive"))
      (node (ref "E17") (pin "7") (pinfunction "O_7") (pintype "output"))
    )
    (net (code "93") (name "Net-(E18A-J)") (class "Default")
      (node (ref "1.0|2.0") (pin "2") (pinfunction "2_2") (pintype "passive"))
      (node (ref "1.5") (pin "1") (pinfunction "1_1") (pintype "passive"))
      (node (ref "E18") (pin "3") (pinfunction "J_3") (pintype "input"))
      (node (ref "E18") (pin "5") (pinfunction "J_5") (pintype "input"))
    )
    (net (code "94") (name "Net-(E18A-K)") (class "Default")
      (node (ref "E18") (pin "1") (pinfunction "K_1") (pintype "input"))
      (node (ref "E18") (pin "8") (pinfunction "~{Q}_8") (pintype "output"))
      (node (ref "E4") (pin "9") (pinfunction "I0_9") (pintype "input"))
    )
    (net (code "95") (name "Net-(E18A-~{Q})") (class "Default")
      (node (ref "1.5") (pin "2") (pinfunction "2_2") (pintype "passive"))
      (node (ref "1.5|2.0-1.0") (pin "1") (pinfunction "1_1") (pintype "passive"))
      (node (ref "E18") (pin "14") (pinfunction "~{Q}_14") (pintype "output"))
    )
    (net (code "96") (name "Net-(Q1-B)") (class "Default")
      (node (ref "Q1") (pin "2") (pinfunction "B_2") (pintype "passive"))
      (node (ref "R35") (pin "1") (pinfunction "1_1") (pintype "passive"))
      (node (ref "R36") (pin "2") (pinfunction "2_2") (pintype "passive"))
    )
    (net (code "97") (name "Net-(Q2-B)") (class "Default")
      (node (ref "Q2") (pin "2") (pinfunction "B_2") (pintype "passive"))
      (node (ref "R33") (pin "1") (pinfunction "1_1") (pintype "passive"))
      (node (ref "R34") (pin "2") (pinfunction "2_2") (pintype "passive"))
    )
    (net (code "98") (name "Net-(Q3-B)") (class "Default")
      (node (ref "Q3") (pin "2") (pinfunction "B_2") (pintype "passive"))
      (node (ref "R31") (pin "1") (pinfunction "1_1") (pintype "passive"))
      (node (ref "R32") (pin "2") (pinfunction "2_2") (pintype "passive"))
    )
    (net (code "99") (name "Net-(Q4-B)") (class "Default")
      (node (ref "Q4") (pin "2") (pinfunction "B_2") (pintype "passive"))
      (node (ref "R29") (pin "1") (pinfunction "1_1") (pintype "passive"))
      (node (ref "R30") (pin "2") (pinfunction "2_2") (pintype "passive"))
    )
    (net (code "100") (name "Net-(Q5-B)") (class "Default")
      (node (ref "Q5") (pin "2") (pinfunction "B_2") (pintype "passive"))
      (node (ref "R27") (pin "1") (pinfunction "1_1") (pintype "passive"))
      (node (ref "R28") (pin "2") (pinfunction "2_2") (pintype "passive"))
    )
    (net (code "101") (name "Net-(Q6-B)") (class "Default")
      (node (ref "Q6") (pin "2") (pinfunction "B_2") (pintype "passive"))
      (node (ref "R25") (pin "1") (pinfunction "1_1") (pintype "passive"))
      (node (ref "R26") (pin "2") (pinfunction "2_2") (pintype "passive"))
    )
    (net (code "102") (name "Net-(Q7-B)") (class "Default")
      (node (ref "Q7") (pin "2") (pinfunction "B_2") (pintype "passive"))
      (node (ref "R23") (pin "1") (pinfunction "1_1") (pintype "passive"))
      (node (ref "R24") (pin "2") (pinfunction "2_2") (pintype "passive"))
    )
    (net (code "103") (name "Net-(Q8-B)") (class "Default")
      (node (ref "Q8") (pin "2") (pinfunction "B_2") (pintype "passive"))
      (node (ref "R21") (pin "1") (pinfunction "1_1") (pintype "passive"))
      (node (ref "R22") (pin "2") (pinfunction "2_2") (pintype "passive"))
    )
    (net (code "104") (name "Net-(Q9-B)") (class "Default")
      (node (ref "Q9") (pin "2") (pinfunction "B_2") (pintype "passive"))
      (node (ref "R19") (pin "1") (pinfunction "1_1") (pintype "passive"))
      (node (ref "R20") (pin "2") (pinfunction "2_2") (pintype "passive"))
    )
    (net (code "105") (name "Net-(Q10-B)") (class "Default")
      (node (ref "Q10") (pin "2") (pinfunction "B_2") (pintype "passive"))
      (node (ref "R17") (pin "1") (pinfunction "1_1") (pintype "passive"))
      (node (ref "R18") (pin "2") (pinfunction "2_2") (pintype "passive"))
    )
    (net (code "106") (name "Net-(Q11-B)") (class "Default")
      (node (ref "Q11") (pin "2") (pinfunction "B_2") (pintype "passive"))
      (node (ref "R15") (pin "1") (pinfunction "1_1") (pintype "passive"))
      (node (ref "R16") (pin "2") (pinfunction "2_2") (pintype "passive"))
    )
    (net (code "107") (name "Net-(Q12-B)") (class "Default")
      (node (ref "D2") (pin "C") (pinfunction "C_C") (pintype "passive"))
      (node (ref "Q12") (pin "2") (pinfunction "B_2") (pintype "passive"))
      (node (ref "R37") (pin "1") (pinfunction "1_1") (pintype "passive"))
    )
    (net (code "108") (name "Net-(U$2BN-1)") (class "Default")
      (node (ref "R1") (pin "1") (pinfunction "1_1") (pintype "passive"))
      (node (ref "U$2") (pin "BS2") (pinfunction "1_BS2") (pintype "bidirectional"))
    )
    (net (code "109") (name "Net-(U$2BP-1)") (class "Default")
      (node (ref "R11") (pin "1") (pinfunction "1_1") (pintype "passive"))
      (node (ref "U$2") (pin "BT2") (pinfunction "1_BT2") (pintype "bidirectional"))
    )
    (net (code "110") (name "Net-(U$2BT-1)") (class "Default")
      (node (ref "R3") (pin "1") (pinfunction "1_1") (pintype "passive"))
      (node (ref "U$2") (pin "BV2") (pinfunction "1_BV2") (pintype "bidirectional"))
    )
    (net (code "111") (name "Net-(U$2H-1)") (class "Default")
      (node (ref "R5") (pin "1") (pinfunction "1_1") (pintype "passive"))
      (node (ref "U$2") (pin "AD2") (pinfunction "1_AD2") (pintype "bidirectional"))
    )
    (net (code "112") (name "Net-(U$2L-1)") (class "Default")
      (node (ref "R9") (pin "2") (pinfunction "2_2") (pintype "passive"))
      (node (ref "U$2") (pin "AF2") (pinfunction "1_AF2") (pintype "bidirectional"))
    )
    (net (code "113") (name "VCC") (class "Default")
      (node (ref "E3") (pin "5") (pinfunction "J_5") (pintype "input"))
      (node (ref "E5") (pin "3") (pinfunction "J_3") (pintype "input"))
      (node (ref "E5") (pin "5") (pinfunction "J_5") (pintype "input"))
      (node (ref "R10") (pin "2") (pinfunction "2_2") (pintype "passive"))
      (node (ref "R12") (pin "2") (pinfunction "2_2") (pintype "passive"))
      (node (ref "R14") (pin "2") (pinfunction "2_2") (pintype "passive"))
      (node (ref "R2") (pin "2") (pinfunction "2_2") (pintype "passive"))
      (node (ref "R4") (pin "2") (pinfunction "2_2") (pintype "passive"))
      (node (ref "R6") (pin "2") (pinfunction "2_2") (pintype "passive"))
      (node (ref "R7") (pin "2") (pinfunction "2_2") (pintype "passive"))
      (node (ref "R8") (pin "2") (pinfunction "2_2") (pintype "passive"))
      (node (ref "U$2") (pin "AJ2") (pinfunction "1_AJ2") (pintype "bidirectional"))
    )
    (net (code "114") (name "unconnected-(E1A-E-Pad2)") (class "Default")
      (node (ref "E1") (pin "2") (pinfunction "E_2") (pintype "output"))
    )
    (net (code "115") (name "unconnected-(E1A-R-Pad12)") (class "Default")
      (node (ref "E1") (pin "12") (pinfunction "R_12") (pintype "passive"))
    )
    (net (code "116") (name "unconnected-(E1B-E-Pad10)") (class "Default")
      (node (ref "E1") (pin "10") (pinfunction "E_10") (pintype "output"))
    )
    (net (code "117") (name "unconnected-(E1B-R-Pad9)") (class "Default")
      (node (ref "E1") (pin "9") (pinfunction "R_9") (pintype "passive"))
    )
    (net (code "118") (name "unconnected-(E2A-O-Pad1)") (class "Default")
      (node (ref "E2") (pin "1") (pinfunction "O_1") (pintype "output"))
    )
    (net (code "119") (name "unconnected-(E2B-O-Pad2)") (class "Default")
      (node (ref "E2") (pin "2") (pinfunction "O_2") (pintype "output"))
    )
    (net (code "120") (name "unconnected-(E2C-O-Pad3)") (class "Default")
      (node (ref "E2") (pin "3") (pinfunction "O_3") (pintype "output"))
    )
    (net (code "121") (name "unconnected-(E2E-O-Pad6)") (class "Default")
      (node (ref "E2") (pin "6") (pinfunction "O_6") (pintype "output"))
    )
    (net (code "122") (name "unconnected-(E3A-Q-Pad13)") (class "Default")
      (node (ref "E3") (pin "13") (pinfunction "Q_13") (pintype "output"))
    )
    (net (code "123") (name "unconnected-(E3B-~{Q}-Pad8)") (class "Default")
      (node (ref "E3") (pin "8") (pinfunction "~{Q}_8") (pintype "output"))
    )
    (net (code "124") (name "unconnected-(E5A-Q-Pad13)") (class "Default")
      (node (ref "E5") (pin "13") (pinfunction "Q_13") (pintype "output"))
    )
    (net (code "125") (name "unconnected-(E15A-~{Q}-Pad14)") (class "Default")
      (node (ref "E15") (pin "14") (pinfunction "~{Q}_14") (pintype "output"))
    )
    (net (code "126") (name "unconnected-(E16A-E-Pad2)") (class "Default")
      (node (ref "E16") (pin "2") (pinfunction "E_2") (pintype "output"))
    )
    (net (code "127") (name "unconnected-(E16A-R-Pad12)") (class "Default")
      (node (ref "E16") (pin "12") (pinfunction "R_12") (pintype "passive"))
    )
    (net (code "128") (name "unconnected-(E16B-E-Pad10)") (class "Default")
      (node (ref "E16") (pin "10") (pinfunction "E_10") (pintype "output"))
    )
    (net (code "129") (name "unconnected-(E16B-R-Pad9)") (class "Default")
      (node (ref "E16") (pin "9") (pinfunction "R_9") (pintype "passive"))
    )
    (net (code "130") (name "unconnected-(E17C-O-Pad3)") (class "Default")
      (node (ref "E17") (pin "3") (pinfunction "O_3") (pintype "output"))
    )
    (net (code "131") (name "unconnected-(E18A-Q-Pad13)") (class "Default")
      (node (ref "E18") (pin "13") (pinfunction "Q_13") (pintype "output"))
    )
  )
)
